# connect.net
KiCad netlist of a schematic drawn in Altium Designer
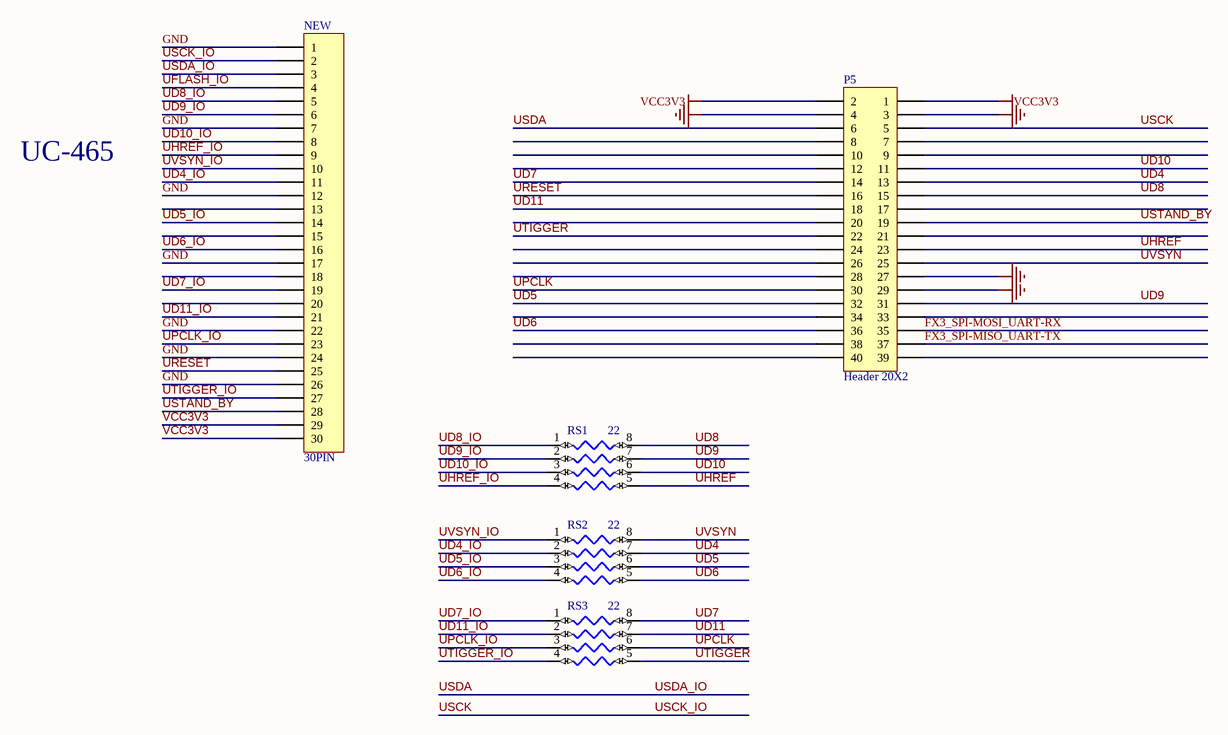
[diagram p0: connect.SchDoc]

(export (version "E")
  (design (tool "Eeschema 10.0.6"))
  (components
    (comp (ref "NEW")
      (value "30PIN")
      (footprint "FH12-30S-0.5SH")
      (description "Header, 30-Pin")
      (fields (field (name "PUBLISHER") "Altium Limited"))
      (libsource (lib "Miscellaneous Connectors") (part "Header 30"))
    )
    (comp (ref "P5")
      (value "Header 20X2")
      (footprint "1.27MM 2*20")
      (description "Header, 20-Pin, Dual row")
      (fields (field (name "PUBLISHER") "Altium Limited"))
      (libsource (lib "Miscellaneous Connectors") (part "Header 20X2"))
    )
    (comp (ref "RS1") (value "22") (footprint "NC06-4") (libsource (lib "*") (part "RN4")))
    (comp (ref "RS2") (value "22") (footprint "NC06-4") (libsource (lib "*") (part "RN4")))
    (comp (ref "RS3") (value "22") (footprint "NC06-4") (libsource (lib "*") (part "RN4")))
  )
  (nets
    (net (code "1") (name "/FX3_SPI-MISO_UART-TX") (class "Default")
      (node (ref "P5") (pin "37") (pinfunction "37_37") (pintype "passive"))
    )
    (net (code "2") (name "/FX3_SPI-MOSI_UART-RX") (class "Default")
      (node (ref "P5") (pin "35") (pinfunction "35_35") (pintype "passive"))
    )
    (net (code "3") (name "/UD4") (class "Default")
      (node (ref "P5") (pin "13") (pinfunction "13_13") (pintype "passive"))
      (node (ref "RS2") (pin "7") (pinfunction "7_7") (pintype "bidirectional"))
    )
    (net (code "4") (name "/UD4_IO") (class "Default")
      (node (ref "NEW") (pin "11") (pinfunction "11_11") (pintype "passive"))
      (node (ref "RS2") (pin "2") (pinfunction "2_2") (pintype "bidirectional"))
    )
    (net (code "5") (name "/UD5") (class "Default")
      (node (ref "P5") (pin "32") (pinfunction "32_32") (pintype "passive"))
      (node (ref "RS2") (pin "6") (pinfunction "6_6") (pintype "bidirectional"))
    )
    (net (code "6") (name "/UD5_IO") (class "Default")
      (node (ref "NEW") (pin "14") (pinfunction "14_14") (pintype "passive"))
      (node (ref "RS2") (pin "3") (pinfunction "3_3") (pintype "bidirectional"))
    )
    (net (code "7") (name "/UD6") (class "Default")
      (node (ref "P5") (pin "36") (pinfunction "36_36") (pintype "passive"))
      (node (ref "RS2") (pin "5") (pinfunction "5_5") (pintype "bidirectional"))
    )
    (net (code "8") (name "/UD6_IO") (class "Default")
      (node (ref "NEW") (pin "16") (pinfunction "16_16") (pintype "passive"))
      (node (ref "RS2") (pin "4") (pinfunction "4_4") (pintype "bidirectional"))
    )
    (net (code "9") (name "/UD7") (class "Default")
      (node (ref "P5") (pin "14") (pinfunction "14_14") (pintype "passive"))
      (node (ref "RS3") (pin "8") (pinfunction "8_8") (pintype "bidirectional"))
    )
    (net (code "10") (name "/UD7_IO") (class "Default")
      (node (ref "NEW") (pin "19") (pinfunction "19_19") (pintype "passive"))
      (node (ref "RS3") (pin "1") (pinfunction "1_1") (pintype "bidirectional"))
    )
    (net (code "11") (name "/UD8") (class "Default")
      (node (ref "P5") (pin "15") (pinfunction "15_15") (pintype "passive"))
      (node (ref "RS1") (pin "8") (pinfunction "8_8") (pintype "bidirectional"))
    )
    (net (code "12") (name "/UD8_IO") (class "Default")
      (node (ref "NEW") (pin "5") (pinfunction "5_5") (pintype "passive"))
      (node (ref "RS1") (pin "1") (pinfunction "1_1") (pintype "bidirectional"))
    )
    (net (code "13") (name "/UD9") (class "Default")
      (node (ref "P5") (pin "31") (pinfunction "31_31") (pintype "passive"))
      (node (ref "RS1") (pin "7") (pinfunction "7_7") (pintype "bidirectional"))
    )
    (net (code "14") (name "/UD9_IO") (class "Default")
      (node (ref "NEW") (pin "6") (pinfunction "6_6") (pintype "passive"))
      (node (ref "RS1") (pin "2") (pinfunction "2_2") (pintype "bidirectional"))
    )
    (net (code "15") (name "/UD10") (class "Default")
      (node (ref "P5") (pin "11") (pinfunction "11_11") (pintype "passive"))
      (node (ref "RS1") (pin "6") (pinfunction "6_6") (pintype "bidirectional"))
    )
    (net (code "16") (name "/UD10_IO") (class "Default")
      (node (ref "NEW") (pin "8") (pinfunction "8_8") (pintype "passive"))
      (node (ref "RS1") (pin "3") (pinfunction "3_3") (pintype "bidirectional"))
    )
    (net (code "17") (name "/UD11") (class "Default")
      (node (ref "P5") (pin "18") (pinfunction "18_18") (pintype "passive"))
      (node (ref "RS3") (pin "7") (pinfunction "7_7") (pintype "bidirectional"))
    )
    (net (code "18") (name "/UD11_IO") (class "Default")
      (node (ref "NEW") (pin "21") (pinfunction "21_21") (pintype "passive"))
      (node (ref "RS3") (pin "2") (pinfunction "2_2") (pintype "bidirectional"))
    )
    (net (code "19") (name "/UFLASH_IO") (class "Default")
      (node (ref "NEW") (pin "4") (pinfunction "4_4") (pintype "passive"))
    )
    (net (code "20") (name "/UHREF") (class "Default")
      (node (ref "P5") (pin "23") (pinfunction "23_23") (pintype "passive"))
      (node (ref "RS1") (pin "5") (pinfunction "5_5") (pintype "bidirectional"))
    )
    (net (code "21") (name "/UHREF_IO") (class "Default")
      (node (ref "NEW") (pin "9") (pinfunction "9_9") (pintype "passive"))
      (node (ref "RS1") (pin "4") (pinfunction "4_4") (pintype "bidirectional"))
    )
    (net (code "22") (name "/UPCLK") (class "Default")
      (node (ref "P5") (pin "30") (pinfunction "30_30") (pintype "passive"))
      (node (ref "RS3") (pin "6") (pinfunction "6_6") (pintype "bidirectional"))
    )
    (net (code "23") (name "/UPCLK_IO") (class "Default")
      (node (ref "NEW") (pin "23") (pinfunction "23_23") (pintype "passive"))
      (node (ref "RS3") (pin "3") (pinfunction "3_3") (pintype "bidirectional"))
    )
    (net (code "24") (name "/URESET") (class "Default")
      (node (ref "NEW") (pin "25") (pinfunction "25_25") (pintype "passive"))
      (node (ref "P5") (pin "16") (pinfunction "16_16") (pintype "passive"))
    )
    (net (code "25") (name "/USCK") (class "Default")
      (node (ref "NEW") (pin "2") (pinfunction "2_2") (pintype "passive"))
      (node (ref "P5") (pin "5") (pinfunction "5_5") (pintype "passive"))
    )
    (net (code "26") (name "/USDA") (class "Default")
      (node (ref "NEW") (pin "3") (pinfunction "3_3") (pintype "passive"))
      (node (ref "P5") (pin "6") (pinfunction "6_6") (pintype "passive"))
    )
    (net (code "27") (name "/USTAND_BY") (class "Default")
      (node (ref "NEW") (pin "28") (pinfunction "28_28") (pintype "passive"))
      (node (ref "P5") (pin "19") (pinfunction "19_19") (pintype "passive"))
    )
    (net (code "28") (name "/UTIGGER") (class "Default")
      (node (ref "P5") (pin "22") (pinfunction "22_22") (pintype "passive"))
      (node (ref "RS3") (pin "5") (pinfunction "5_5") (pintype "bidirectional"))
    )
    (net (code "29") (name "/UTIGGER_IO") (class "Default")
      (node (ref "NEW") (pin "27") (pinfunction "27_27") (pintype "passive"))
      (node (ref "RS3") (pin "4") (pinfunction "4_4") (pintype "bidirectional"))
    )
    (net (code "30") (name "/UVSYN") (class "Default")
      (node (ref "P5") (pin "25") (pinfunction "25_25") (pintype "passive"))
      (node (ref "RS2") (pin "8") (pinfunction "8_8") (pintype "bidirectional"))
    )
    (net (code "31") (name "/UVSYN_IO") (class "Default")
      (node (ref "NEW") (pin "10") (pinfunction "10_10") (pintype "passive"))
      (node (ref "RS2") (pin "1") (pinfunction "1_1") (pintype "bidirectional"))
    )
    (net (code "32") (name "GND") (class "Default")
      (node (ref "NEW") (pin "1") (pinfunction "1_1") (pintype "passive"))
      (node (ref "NEW") (pin "12") (pinfunction "12_12") (pintype "passive"))
      (node (ref "NEW") (pin "17") (pinfunction "17_17") (pintype "passive"))
      (node (ref "NEW") (pin "22") (pinfunction "22_22") (pintype "passive"))
      (node (ref "NEW") (pin "24") (pinfunction "24_24") (pintype "passive"))
      (node (ref "NEW") (pin "26") (pinfunction "26_26") (pintype "passive"))
      (node (ref "NEW") (pin "7") (pinfunction "7_7") (pintype "passive"))
      (node (ref "P5") (pin "27") (pinfunction "27_27") (pintype "passive"))
      (node (ref "P5") (pin "29") (pinfunction "29_29") (pintype "passive"))
      (node (ref "P5") (pin "3") (pinfunction "3_3") (pintype "passive"))
      (node (ref "P5") (pin "4") (pinfunction "4_4") (pintype "passive"))
    )
    (net (code "33") (name "VCC3V3") (class "Default")
      (node (ref "NEW") (pin "29") (pinfunction "29_29") (pintype "passive"))
      (node (ref "NEW") (pin "30") (pinfunction "30_30") (pintype "passive"))
      (node (ref "P5") (pin "1") (pinfunction "1_1") (pintype "passive"))
      (node (ref "P5") (pin "2") (pinfunction "2_2") (pintype "passive"))
    )
    (net (code "34") (name "unconnected-(NEW-Pad13)") (class "Default")
      (node (ref "NEW") (pin "13") (pinfunction "13_13") (pintype "passive"))
    )
    (net (code "35") (name "unconnected-(NEW-Pad15)") (class "Default")
      (node (ref "NEW") (pin "15") (pinfunction "15_15") (pintype "passive"))
    )
    (net (code "36") (name "unconnected-(NEW-Pad18)") (class "Default")
      (node (ref "NEW") (pin "18") (pinfunction "18_18") (pintype "passive"))
    )
    (net (code "37") (name "unconnected-(NEW-Pad20)") (class "Default")
      (node (ref "NEW") (pin "20") (pinfunction "20_20") (pintype "passive"))
    )
    (net (code "38") (name "unconnected-(P5-Pad7)") (class "Default")
      (node (ref "P5") (pin "7") (pinfunction "7_7") (pintype "passive"))
    )
    (net (code "39") (name "unconnected-(P5-Pad8)") (class "Default")
      (node (ref "P5") (pin "8") (pinfunction "8_8") (pintype "passive"))
    )
    (net (code "40") (name "unconnected-(P5-Pad9)") (class "Default")
      (node (ref "P5") (pin "9") (pinfunction "9_9") (pintype "passive"))
    )
    (net (code "41") (name "unconnected-(P5-Pad10)") (class "Default")
      (node (ref "P5") (pin "10") (pinfunction "10_10") (pintype "passive"))
    )
    (net (code "42") (name "unconnected-(P5-Pad12)") (class "Default")
      (node (ref "P5") (pin "12") (pinfunction "12_12") (pintype "passive"))
    )
    (net (code "43") (name "unconnected-(P5-Pad17)") (class "Default")
      (node (ref "P5") (pin "17") (pinfunction "17_17") (pintype "passive"))
    )
    (net (code "44") (name "unconnected-(P5-Pad20)") (class "Default")
      (node (ref "P5") (pin "20") (pinfunction "20_20") (pintype "passive"))
    )
    (net (code "45") (name "unconnected-(P5-Pad21)") (class "Default")
      (node (ref "P5") (pin "21") (pinfunction "21_21") (pintype "passive"))
    )
    (net (code "46") (name "unconnected-(P5-Pad24)") (class "Default")
      (node (ref "P5") (pin "24") (pinfunction "24_24") (pintype "passive"))
    )
    (net (code "47") (name "unconnected-(P5-Pad26)") (class "Default")
      (node (ref "P5") (pin "26") (pinfunction "26_26") (pintype "passive"))
    )
    (net (code "48") (name "unconnected-(P5-Pad28)") (class "Default")
      (node (ref "P5") (pin "28") (pinfunction "28_28") (pintype "passive"))
    )
    (net (code "49") (name "unconnected-(P5-Pad33)") (class "Default")
      (node (ref "P5") (pin "33") (pinfunction "33_33") (pintype "passive"))
    )
    (net (code "50") (name "unconnected-(P5-Pad34)") (class "Default")
      (node (ref "P5") (pin "34") (pinfunction "34_34") (pintype "passive"))
    )
    (net (code "51") (name "unconnected-(P5-Pad38)") (class "Default")
      (node (ref "P5") (pin "38") (pinfunction "38_38") (pintype "passive"))
    )
    (net (code "52") (name "unconnected-(P5-Pad39)") (class "Default")
      (node (ref "P5") (pin "39") (pinfunction "39_39") (pintype "passive"))
    )
    (net (code "53") (name "unconnected-(P5-Pad40)") (class "Default")
      (node (ref "P5") (pin "40") (pinfunction "40_40") (pintype "passive"))
    )
  )
)
